# cm_filter_ch0_b.net
KiCad netlist of a schematic drawn in Altium Designer
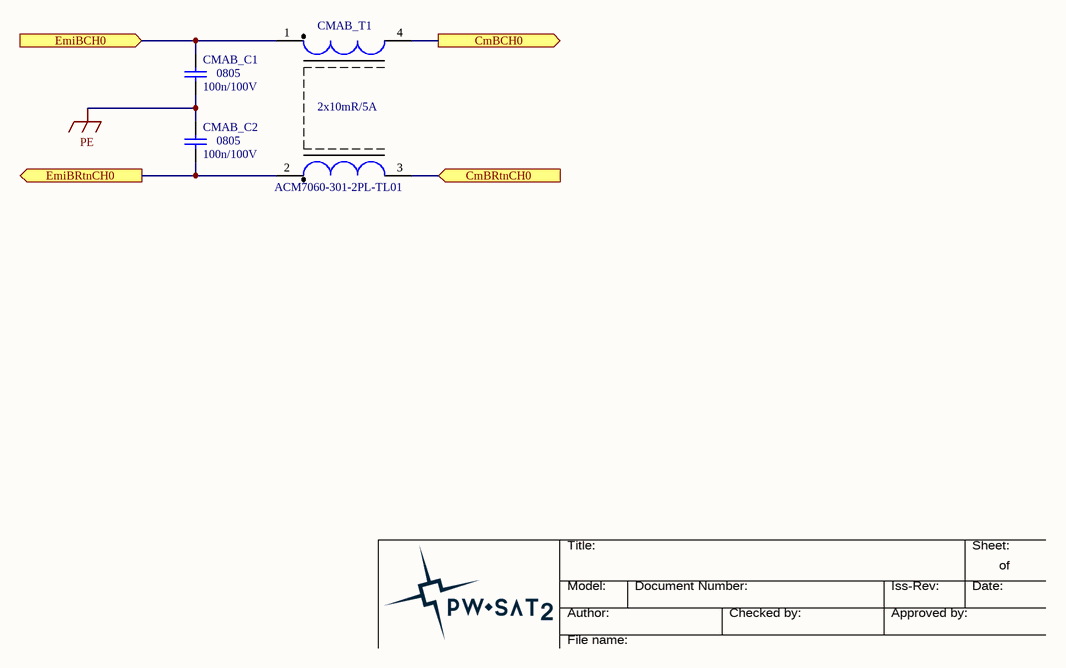
[diagram p0: cm_filter_ch0_b.SchDoc]

(export (version "E")
  (design (tool "Eeschema 10.0.6"))
  (components
    (comp (ref "CMAB_C1")
      (value "100n/100V")
      (footprint "SMD_Capacitor_0805")
      (description "Ceramic Cap Kemet COTS 100n/100V X7R 0805")
      (fields
        (field (name "MANUFACTURERPARTNUMBER") "C0805T104K1RCLTU")
        (field (name "MANUFACTURER") "Kemet")
        (field (name "PACKAGE") "0805")
      )
      (libsource (lib "capacitors") (part "Cer_C0805T104K1RCLTU"))
    )
    (comp (ref "CMAB_C2")
      (value "100n/100V")
      (footprint "SMD_Capacitor_0805")
      (description "Ceramic Cap Kemet COTS 100n/100V X7R 0805")
      (fields
        (field (name "MANUFACTURERPARTNUMBER") "C0805T104K1RCLTU")
        (field (name "MANUFACTURER") "Kemet")
        (field (name "PACKAGE") "0805")
      )
      (libsource (lib "capacitors") (part "Cer_C0805T104K1RCLTU"))
    )
    (comp (ref "CMAB_T1")
      (value "2x10mR/5A")
      (footprint "TDK_ACM7060")
      (description "TDK ACM7060-301 Common Mode Choke")
      (fields
        (field (name "MANUFACTURER") "TDK")
        (field (name "MANUFACTURERPARTNUMBER") "ACM7060-301-2PL-TL01")
      )
      (libsource (lib "inductors") (part "ACM7060-301-2PL-TL01"))
    )
  )
  (nets
    (net (code "1") (name "/CmBCH0") (class "Default")
      (node (ref "CMAB_T1") (pin "4") (pinfunction "4_4") (pintype "passive"))
    )
    (net (code "2") (name "/CmBRtnCH0") (class "Default")
      (node (ref "CMAB_T1") (pin "3") (pinfunction "3_3") (pintype "passive"))
    )
    (net (code "3") (name "/EmiBCH0") (class "Default")
      (node (ref "CMAB_C1") (pin "1") (pinfunction "1_1") (pintype "passive"))
      (node (ref "CMAB_T1") (pin "1") (pinfunction "1_1") (pintype "passive"))
    )
    (net (code "4") (name "/EmiBRtnCH0") (class "Default")
      (node (ref "CMAB_C2") (pin "2") (pinfunction "2_2") (pintype "passive"))
      (node (ref "CMAB_T1") (pin "2") (pinfunction "2_2") (pintype "passive"))
    )
    (net (code "5") (name "PE") (class "Default")
      (node (ref "CMAB_C1") (pin "2") (pinfunction "2_2") (pintype "passive"))
      (node (ref "CMAB_C2") (pin "1") (pinfunction "1_1") (pintype "passive"))
    )
  )
)
